# Sheet1.net
KiCad netlist of a schematic drawn in Altium Designer
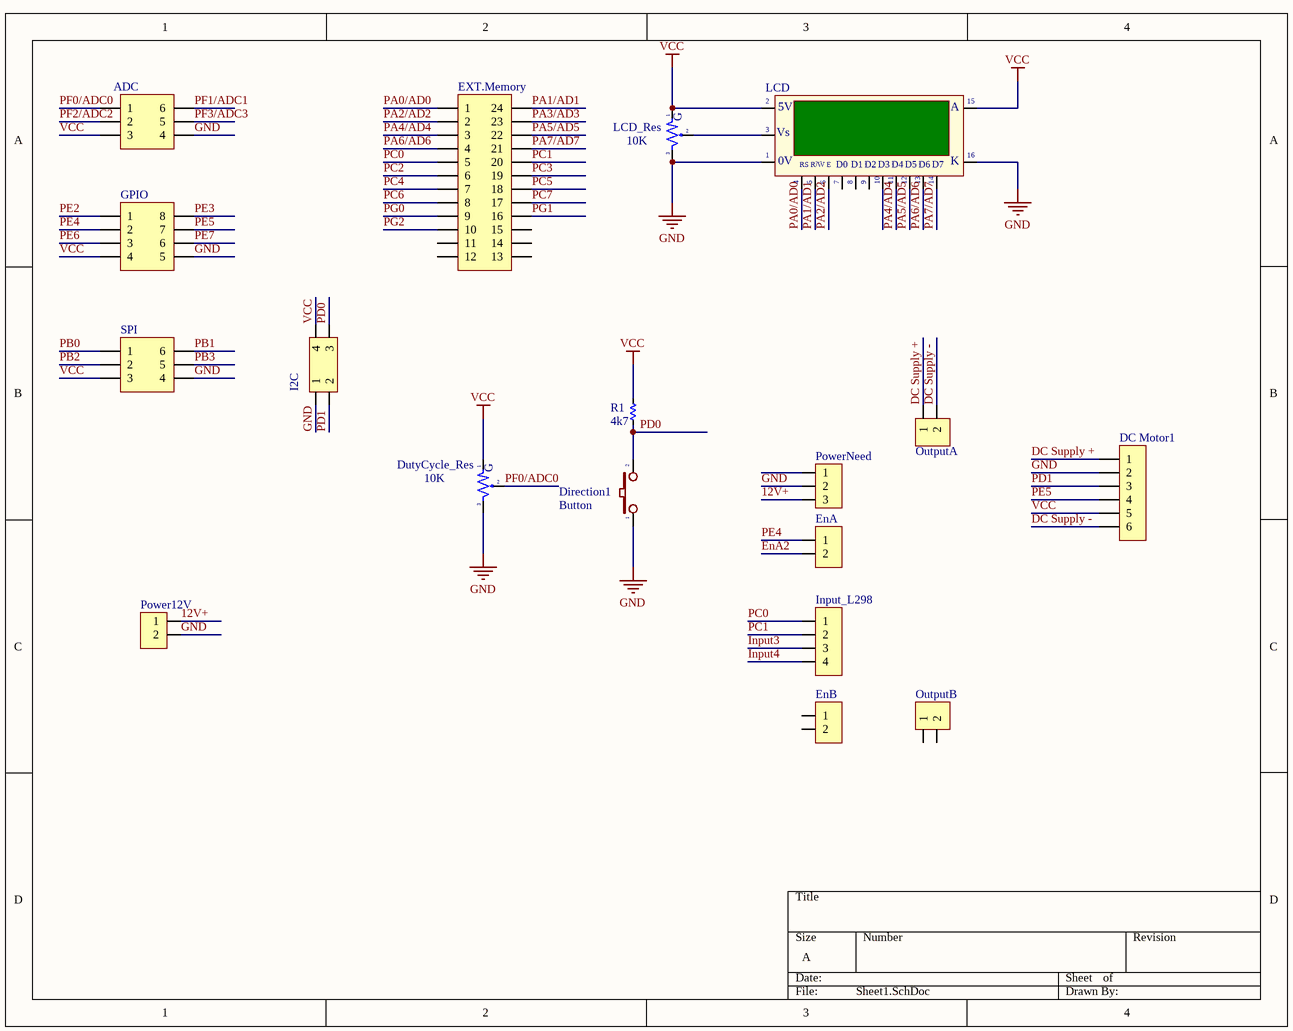
[diagram p0: Sheet1.SchDoc]

(export (version "E")
  (design (tool "Eeschema 10.0.6"))
  (components
    (comp (ref "ADC")
      (value "~")
      (footprint "JP3-C2T")
      (description "WR-PHD 2.54 mm Dual Socket Header")
      (fields
        (field (name "MANUFACTURER") "Würth Elektronik eiSos GmbH")
        (field (name "PARTNO") "61300621821")
        (field (name "CREATED BY") "Karrer Zheng")
      )
      (libsource (lib "LIBRARY") (part "JP3x2"))
    )
    (comp (ref "DC Motor1")
      (value "~")
      (footprint "J6-C1T")
      (description "WR-PHD 2.00 mm Socket Header")
      (fields
        (field (name "MANUFACTURER") "Würth Elektronik eiSos GmbH")
        (field (name "PARTNO") "62000611821")
        (field (name "CREATED BY") "Karrer Zheng")
      )
      (libsource (lib "LIBRARY") (part "JP6x1-2.0"))
    )
    (comp (ref "Direction1")
      (value "Button")
      (footprint "SW-DIP1")
      (description "Switch button 2 pin")
      (libsource (lib "LIBRARY") (part "SW2"))
    )
    (comp (ref "DutyCycle_Res")
      (value "10K")
      (footprint "VR-S1")
      (description "Var Resistor")
      (libsource (lib "LIBRARY") (part "VR-S"))
    )
    (comp (ref "EnA")
      (value "~")
      (footprint "JP2-D1T")
      (description "WR-PHD 2.54 mm Angled Socket Header")
      (fields
        (field (name "MANUFACTURER") "Würth Elektronik eiSos GmbH")
        (field (name "PARTNO") "613002143121")
        (field (name "CREATED BY") "Karrer Zheng")
      )
      (libsource (lib "LIBRARY") (part "JP2"))
    )
    (comp (ref "EnB")
      (value "~")
      (footprint "JP2-D1T")
      (description "WR-PHD 2.54 mm Angled Socket Header")
      (fields
        (field (name "MANUFACTURER") "Würth Elektronik eiSos GmbH")
        (field (name "PARTNO") "613002143121")
        (field (name "CREATED BY") "Karrer Zheng")
      )
      (libsource (lib "LIBRARY") (part "JP2"))
    )
    (comp (ref "EXT.Memory")
      (value "~")
      (footprint "JP12-C2T")
      (description "WR-PHD 2.54 mm Dual Socket Header")
      (fields
        (field (name "MANUFACTURER") "Würth Elektronik eiSos GmbH")
        (field (name "PARTNO") "61302421821")
        (field (name "CREATED BY") "Karrer Zheng")
      )
      (libsource (lib "LIBRARY") (part "JP12x2"))
    )
    (comp (ref "GPIO")
      (value "~")
      (footprint "JP4-C2T")
      (description "WR-PHD 2.54 mm Dual Socket Header")
      (fields
        (field (name "MANUFACTURER") "Würth Elektronik eiSos GmbH")
        (field (name "PARTNO") "61300821821")
        (field (name "CREATED BY") "Karrer Zheng")
      )
      (libsource (lib "LIBRARY") (part "JP4x2"))
    )
    (comp (ref "I2C")
      (value "~")
      (footprint "JP2-C2T")
      (description "WR-PHD 2.54 mm Dual Socket Header")
      (fields
        (field (name "MANUFACTURER") "Würth Elektronik eiSos GmbH")
        (field (name "PARTNO") "61300421821")
        (field (name "CREATED BY") "Karrer Zheng")
      )
      (libsource (lib "LIBRARY") (part "JP2x2"))
    )
    (comp (ref "Input_L298")
      (value "~")
      (footprint "JP4-C1T")
      (description "WR-PHD 2.54 mm Angled Socket Header")
      (fields
        (field (name "MANUFACTURER") "Würth Elektronik eiSos GmbH")
        (field (name "PARTNO") "613004143121")
        (field (name "CREATED BY") "Karrer Zheng")
      )
      (libsource (lib "LIBRARY") (part "JP4"))
    )
    (comp (ref "LCD")
      (value "~")
      (footprint "LCD16X2")
      (description "LCD dipslay 16 char, 2 line")
      (libsource (lib "LIBRARY") (part "LCD16x2A"))
    )
    (comp (ref "LCD_Res")
      (value "10K")
      (footprint "VR-S1")
      (description "Var Resistor")
      (libsource (lib "LIBRARY") (part "VR-S"))
    )
    (comp (ref "OutputA")
      (value "~")
      (footprint "Header2")
      (description "Header IDC, 2 x 1 Pin Vertical 2.54mm Pitch (Non-Boxed, Male)")
      (fields
        (field (name "MANUFACTURER") "Würth Elektronik eiSos GmbH")
        (field (name "PARTNO") "613002143121")
        (field (name "CREATED BY") "Karrer Zheng")
      )
      (libsource (lib "") (part "Header2_1"))
    )
    (comp (ref "OutputB")
      (value "~")
      (footprint "Header2")
      (description "Header IDC, 2 x 1 Pin Vertical 2.54mm Pitch (Non-Boxed, Male)")
      (fields
        (field (name "MANUFACTURER") "Würth Elektronik eiSos GmbH")
        (field (name "PARTNO") "613002143121")
        (field (name "CREATED BY") "Karrer Zheng")
      )
      (libsource (lib "LIBRARY") (part "Header2"))
    )
    (comp (ref "Power12V")
      (value "~")
      (footprint "Header2")
      (description "Header IDC, 2 x 1 Pin Vertical 2.54mm Pitch (Non-Boxed, Male)")
      (fields
        (field (name "MANUFACTURER") "Würth Elektronik eiSos GmbH")
        (field (name "PARTNO") "613002143121")
        (field (name "CREATED BY") "Karrer Zheng")
      )
      (libsource (lib "") (part "Header2_2"))
    )
    (comp (ref "PowerNeed")
      (value "~")
      (footprint "HDR3")
      (description "Header IDC, 3 x 1 Pin Vertical 2.54mm Pitch (Non-Boxed, Male)")
      (fields
        (field (name "MANUFACTURER") "Würth Elektronik eiSos GmbH")
        (field (name "PARTNO") "613002143121")
        (field (name "CREATED BY") "Karrer Zheng")
      )
      (libsource (lib "LIBRARY") (part "Header3"))
    )
    (comp (ref "R1")
      (value "4k7")
      (footprint "RES-1/2W")
      (description "Res")
      (fields
        (field (name "MANUFACTURER") "Generic Components")
        (field (name "PUBLISHER") "Altium Hobart Technology Centre")
      )
      (libsource (lib "LIBRARY") (part "Res"))
    )
    (comp (ref "SPI")
      (value "~")
      (footprint "JP3-C2T")
      (description "WR-PHD 2.54 mm Dual Socket Header")
      (fields
        (field (name "MANUFACTURER") "Würth Elektronik eiSos GmbH")
        (field (name "PARTNO") "61300621821")
        (field (name "CREATED BY") "Karrer Zheng")
      )
      (libsource (lib "LIBRARY") (part "JP3x2"))
    )
  )
  (nets
    (net (code "1") (name "/12V+") (class "Default")
      (node (ref "Power12V") (pin "1") (pinfunction "1_1") (pintype "passive"))
      (node (ref "PowerNeed") (pin "3") (pinfunction "3_3") (pintype "passive"))
    )
    (net (code "2") (name "/DC Supply +") (class "Default")
      (node (ref "DC Motor1") (pin "1") (pinfunction "1_1") (pintype "passive"))
      (node (ref "OutputA") (pin "1") (pinfunction "1_1") (pintype "passive"))
    )
    (net (code "3") (name "/DC Supply -") (class "Default")
      (node (ref "DC Motor1") (pin "6") (pinfunction "6_6") (pintype "passive"))
      (node (ref "OutputA") (pin "2") (pinfunction "2_2") (pintype "passive"))
    )
    (net (code "4") (name "/EnA2") (class "Default")
      (node (ref "EnA") (pin "2") (pinfunction "2_2") (pintype "passive"))
    )
    (net (code "5") (name "/Input3") (class "Default")
      (node (ref "Input_L298") (pin "3") (pinfunction "3_3") (pintype "passive"))
    )
    (net (code "6") (name "/Input4") (class "Default")
      (node (ref "Input_L298") (pin "4") (pinfunction "4_4") (pintype "passive"))
    )
    (net (code "7") (name "/PA0{slash}AD0") (class "Default")
      (node (ref "EXT.Memory") (pin "1") (pinfunction "1_1") (pintype "passive"))
      (node (ref "LCD") (pin "4") (pinfunction "RS_4") (pintype "passive"))
    )
    (net (code "8") (name "/PA1{slash}AD1") (class "Default")
      (node (ref "EXT.Memory") (pin "24") (pinfunction "24_24") (pintype "passive"))
      (node (ref "LCD") (pin "5") (pinfunction "R/~{W}_5") (pintype "passive"))
    )
    (net (code "9") (name "/PA2{slash}AD2") (class "Default")
      (node (ref "EXT.Memory") (pin "2") (pinfunction "2_2") (pintype "passive"))
      (node (ref "LCD") (pin "6") (pinfunction "~{EN}_6") (pintype "passive"))
    )
    (net (code "10") (name "/PA3{slash}AD3") (class "Default")
      (node (ref "EXT.Memory") (pin "23") (pinfunction "23_23") (pintype "passive"))
    )
    (net (code "11") (name "/PA4{slash}AD4") (class "Default")
      (node (ref "EXT.Memory") (pin "3") (pinfunction "3_3") (pintype "passive"))
      (node (ref "LCD") (pin "11") (pinfunction "D4_11") (pintype "passive"))
    )
    (net (code "12") (name "/PA5{slash}AD5") (class "Default")
      (node (ref "EXT.Memory") (pin "22") (pinfunction "22_22") (pintype "passive"))
      (node (ref "LCD") (pin "12") (pinfunction "D5_12") (pintype "passive"))
    )
    (net (code "13") (name "/PA6{slash}AD6") (class "Default")
      (node (ref "EXT.Memory") (pin "4") (pinfunction "4_4") (pintype "passive"))
      (node (ref "LCD") (pin "13") (pinfunction "D6_13") (pintype "passive"))
    )
    (net (code "14") (name "/PA7{slash}AD7") (class "Default")
      (node (ref "EXT.Memory") (pin "21") (pinfunction "21_21") (pintype "passive"))
      (node (ref "LCD") (pin "14") (pinfunction "D7_14") (pintype "passive"))
    )
    (net (code "15") (name "/PB0") (class "Default")
      (node (ref "SPI") (pin "1") (pinfunction "1_1") (pintype "passive"))
    )
    (net (code "16") (name "/PB1") (class "Default")
      (node (ref "SPI") (pin "6") (pinfunction "6_6") (pintype "passive"))
    )
    (net (code "17") (name "/PB2") (class "Default")
      (node (ref "SPI") (pin "2") (pinfunction "2_2") (pintype "passive"))
    )
    (net (code "18") (name "/PB3") (class "Default")
      (node (ref "SPI") (pin "5") (pinfunction "5_5") (pintype "passive"))
    )
    (net (code "19") (name "/PC0") (class "Default")
      (node (ref "EXT.Memory") (pin "5") (pinfunction "5_5") (pintype "passive"))
      (node (ref "Input_L298") (pin "1") (pinfunction "1_1") (pintype "passive"))
    )
    (net (code "20") (name "/PC1") (class "Default")
      (node (ref "EXT.Memory") (pin "20") (pinfunction "20_20") (pintype "passive"))
      (node (ref "Input_L298") (pin "2") (pinfunction "2_2") (pintype "passive"))
    )
    (net (code "21") (name "/PC2") (class "Default")
      (node (ref "EXT.Memory") (pin "6") (pinfunction "6_6") (pintype "passive"))
    )
    (net (code "22") (name "/PC3") (class "Default")
      (node (ref "EXT.Memory") (pin "19") (pinfunction "19_19") (pintype "passive"))
    )
    (net (code "23") (name "/PC4") (class "Default")
      (node (ref "EXT.Memory") (pin "7") (pinfunction "7_7") (pintype "passive"))
    )
    (net (code "24") (name "/PC5") (class "Default")
      (node (ref "EXT.Memory") (pin "18") (pinfunction "18_18") (pintype "passive"))
    )
    (net (code "25") (name "/PC6") (class "Default")
      (node (ref "EXT.Memory") (pin "8") (pinfunction "8_8") (pintype "passive"))
    )
    (net (code "26") (name "/PC7") (class "Default")
      (node (ref "EXT.Memory") (pin "17") (pinfunction "17_17") (pintype "passive"))
    )
    (net (code "27") (name "/PD0") (class "Default")
      (node (ref "Direction1") (pin "2") (pinfunction "2_2") (pintype "passive"))
      (node (ref "I2C") (pin "3") (pinfunction "3_3") (pintype "passive"))
      (node (ref "R1") (pin "2") (pinfunction "2_2") (pintype "passive"))
    )
    (net (code "28") (name "/PD1") (class "Default")
      (node (ref "DC Motor1") (pin "3") (pinfunction "3_3") (pintype "passive"))
      (node (ref "I2C") (pin "2") (pinfunction "2_2") (pintype "passive"))
    )
    (net (code "29") (name "/PE2") (class "Default")
      (node (ref "GPIO") (pin "1") (pinfunction "1_1") (pintype "passive"))
    )
    (net (code "30") (name "/PE3") (class "Default")
      (node (ref "GPIO") (pin "8") (pinfunction "8_8") (pintype "passive"))
    )
    (net (code "31") (name "/PE4") (class "Default")
      (node (ref "EnA") (pin "1") (pinfunction "1_1") (pintype "passive"))
      (node (ref "GPIO") (pin "2") (pinfunction "2_2") (pintype "passive"))
    )
    (net (code "32") (name "/PE5") (class "Default")
      (node (ref "DC Motor1") (pin "4") (pinfunction "4_4") (pintype "passive"))
      (node (ref "GPIO") (pin "7") (pinfunction "7_7") (pintype "passive"))
    )
    (net (code "33") (name "/PE6") (class "Default")
      (node (ref "GPIO") (pin "3") (pinfunction "3_3") (pintype "passive"))
    )
    (net (code "34") (name "/PE7") (class "Default")
      (node (ref "GPIO") (pin "6") (pinfunction "6_6") (pintype "passive"))
    )
    (net (code "35") (name "/PF0{slash}ADC0") (class "Default")
      (node (ref "ADC") (pin "1") (pinfunction "1_1") (pintype "passive"))
      (node (ref "DutyCycle_Res") (pin "2") (pinfunction "2_2") (pintype "passive"))
    )
    (net (code "36") (name "/PF1{slash}ADC1") (class "Default")
      (node (ref "ADC") (pin "6") (pinfunction "6_6") (pintype "passive"))
    )
    (net (code "37") (name "/PF2{slash}ADC2") (class "Default")
      (node (ref "ADC") (pin "2") (pinfunction "2_2") (pintype "passive"))
    )
    (net (code "38") (name "/PF3{slash}ADC3") (class "Default")
      (node (ref "ADC") (pin "5") (pinfunction "5_5") (pintype "passive"))
    )
    (net (code "39") (name "/PG0") (class "Default")
      (node (ref "EXT.Memory") (pin "9") (pinfunction "9_9") (pintype "passive"))
    )
    (net (code "40") (name "/PG1") (class "Default")
      (node (ref "EXT.Memory") (pin "16") (pinfunction "16_16") (pintype "passive"))
    )
    (net (code "41") (name "/PG2") (class "Default")
      (node (ref "EXT.Memory") (pin "10") (pinfunction "10_10") (pintype "passive"))
    )
    (net (code "42") (name "GND") (class "Default")
      (node (ref "ADC") (pin "4") (pinfunction "4_4") (pintype "passive"))
      (node (ref "DC Motor1") (pin "2") (pinfunction "2_2") (pintype "passive"))
      (node (ref "Direction1") (pin "1") (pinfunction "1_1") (pintype "passive"))
      (node (ref "DutyCycle_Res") (pin "3") (pinfunction "3_3") (pintype "passive"))
      (node (ref "GPIO") (pin "5") (pinfunction "5_5") (pintype "passive"))
      (node (ref "I2C") (pin "1") (pinfunction "1_1") (pintype "passive"))
      (node (ref "LCD") (pin "1") (pinfunction "GND_1") (pintype "passive"))
      (node (ref "LCD") (pin "16") (pinfunction "K_16") (pintype "passive"))
      (node (ref "LCD_Res") (pin "3") (pinfunction "3_3") (pintype "passive"))
      (node (ref "Power12V") (pin "2") (pinfunction "2_2") (pintype "passive"))
      (node (ref "PowerNeed") (pin "2") (pinfunction "2_2") (pintype "passive"))
      (node (ref "SPI") (pin "4") (pinfunction "4_4") (pintype "passive"))
    )
    (net (code "43") (name "Net-(LCD-VEE)") (class "Default")
      (node (ref "LCD") (pin "3") (pinfunction "VEE_3") (pintype "passive"))
      (node (ref "LCD_Res") (pin "2") (pinfunction "2_2") (pintype "passive"))
    )
    (net (code "44") (name "VCC") (class "Default")
      (node (ref "ADC") (pin "3") (pinfunction "3_3") (pintype "passive"))
      (node (ref "DC Motor1") (pin "5") (pinfunction "5_5") (pintype "passive"))
      (node (ref "DutyCycle_Res") (pin "1") (pinfunction "1_1") (pintype "passive"))
      (node (ref "GPIO") (pin "4") (pinfunction "4_4") (pintype "passive"))
      (node (ref "I2C") (pin "4") (pinfunction "4_4") (pintype "passive"))
      (node (ref "LCD") (pin "15") (pinfunction "A_15") (pintype "passive"))
      (node (ref "LCD") (pin "2") (pinfunction "VDD_2") (pintype "passive"))
      (node (ref "LCD_Res") (pin "1") (pinfunction "1_1") (pintype "passive"))
      (node (ref "R1") (pin "1") (pinfunction "1_1") (pintype "passive"))
      (node (ref "SPI") (pin "3") (pinfunction "3_3") (pintype "passive"))
    )
    (net (code "45") (name "unconnected-(EXT.Memory-Pad11)") (class "Default")
      (node (ref "EXT.Memory") (pin "11") (pinfunction "11_11") (pintype "passive"))
    )
    (net (code "46") (name "unconnected-(EXT.Memory-Pad12)") (class "Default")
      (node (ref "EXT.Memory") (pin "12") (pinfunction "12_12") (pintype "passive"))
    )
    (net (code "47") (name "unconnected-(EXT.Memory-Pad13)") (class "Default")
      (node (ref "EXT.Memory") (pin "13") (pinfunction "13_13") (pintype "passive"))
    )
    (net (code "48") (name "unconnected-(EXT.Memory-Pad14)") (class "Default")
      (node (ref "EXT.Memory") (pin "14") (pinfunction "14_14") (pintype "passive"))
    )
    (net (code "49") (name "unconnected-(EXT.Memory-Pad15)") (class "Default")
      (node (ref "EXT.Memory") (pin "15") (pinfunction "15_15") (pintype "passive"))
    )
    (net (code "50") (name "unconnected-(EnB-Pad1)") (class "Default")
      (node (ref "EnB") (pin "1") (pinfunction "1_1") (pintype "passive"))
    )
    (net (code "51") (name "unconnected-(EnB-Pad2)") (class "Default")
      (node (ref "EnB") (pin "2") (pinfunction "2_2") (pintype "passive"))
    )
    (net (code "52") (name "unconnected-(LCD-D0-Pad7)") (class "Default")
      (node (ref "LCD") (pin "7") (pinfunction "D0_7") (pintype "passive"))
    )
    (net (code "53") (name "unconnected-(LCD-D1-Pad8)") (class "Default")
      (node (ref "LCD") (pin "8") (pinfunction "D1_8") (pintype "passive"))
    )
    (net (code "54") (name "unconnected-(LCD-D2-Pad9)") (class "Default")
      (node (ref "LCD") (pin "9") (pinfunction "D2_9") (pintype "passive"))
    )
    (net (code "55") (name "unconnected-(LCD-D3-Pad10)") (class "Default")
      (node (ref "LCD") (pin "10") (pinfunction "D3_10") (pintype "passive"))
    )
    (net (code "56") (name "unconnected-(OutputB-Pad1)") (class "Default")
      (node (ref "OutputB") (pin "1") (pinfunction "1_1") (pintype "passive"))
    )
    (net (code "57") (name "unconnected-(OutputB-Pad2)") (class "Default")
      (node (ref "OutputB") (pin "2") (pinfunction "2_2") (pintype "passive"))
    )
    (net (code "58") (name "unconnected-(PowerNeed-Pad1)") (class "Default")
      (node (ref "PowerNeed") (pin "1") (pinfunction "1_1") (pintype "passive"))
    )
  )
)
